# 5_SiPM.net
KiCad netlist of a schematic drawn in Altium Designer
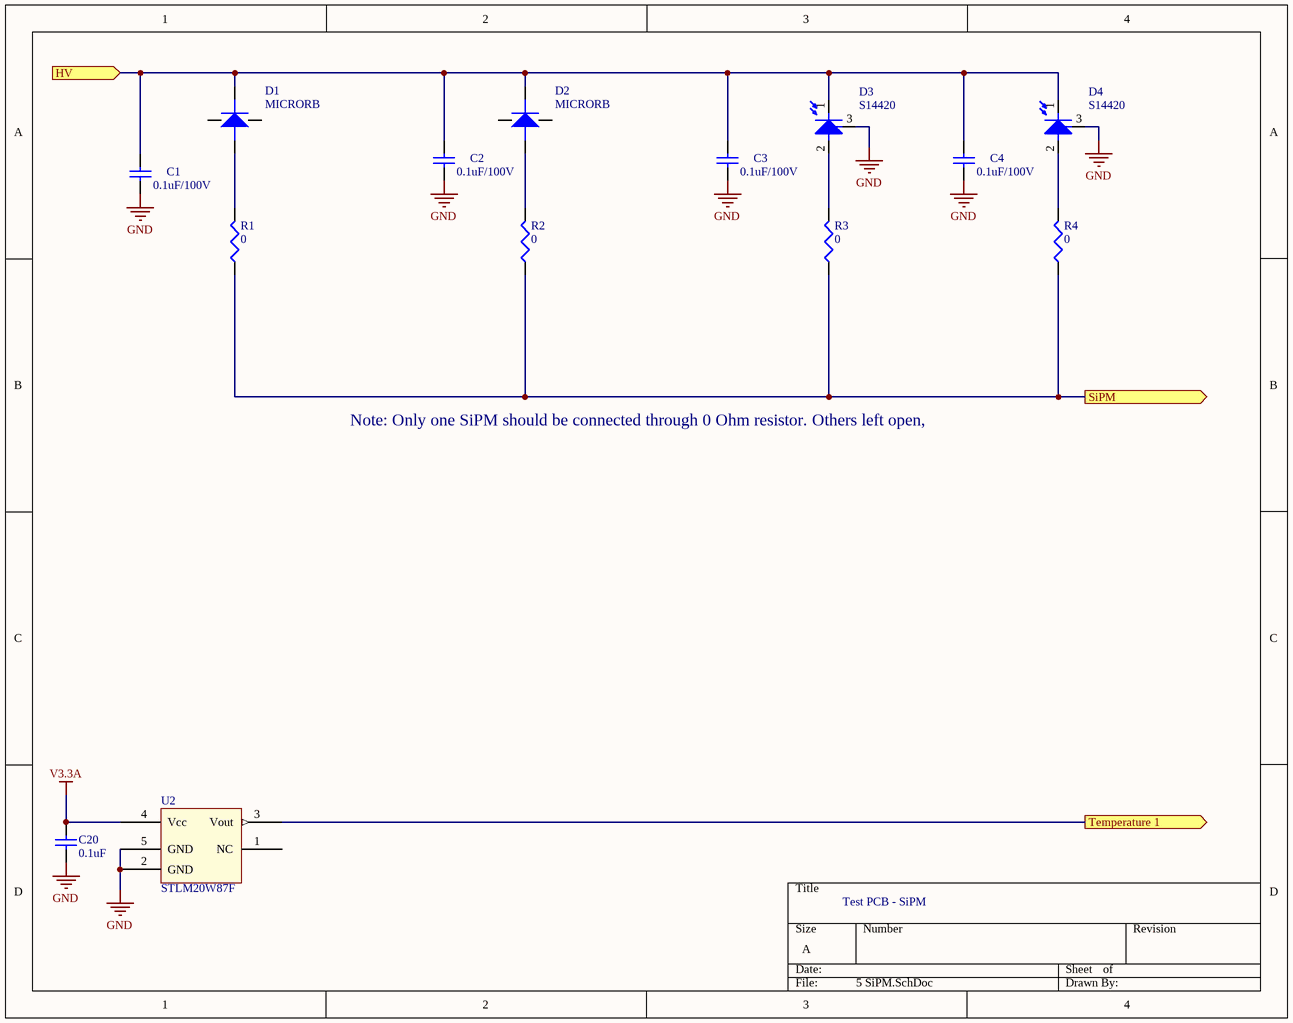
[diagram p0: 5 SiPM.SchDoc]

(export (version "E")
  (design (tool "Eeschema 10.0.6"))
  (components
    (comp (ref "C1")
      (value "0.1uF/100V")
      (footprint "C0603")
      (description "Capacitor, SM")
      (fields (field (name "PUBLISHER") "Altium Limited"))
      (libsource (lib "Graylark") (part "Cap SM"))
    )
    (comp (ref "C2")
      (value "0.1uF/100V")
      (footprint "C0603")
      (description "Capacitor, SM")
      (fields (field (name "PUBLISHER") "Altium Limited"))
      (libsource (lib "Graylark") (part "Cap SM"))
    )
    (comp (ref "C3")
      (value "0.1uF/100V")
      (footprint "C0603")
      (description "Capacitor, SM")
      (fields (field (name "PUBLISHER") "Altium Limited"))
      (libsource (lib "Graylark") (part "Cap SM"))
    )
    (comp (ref "C4")
      (value "0.1uF/100V")
      (footprint "C0603")
      (description "Capacitor, SM")
      (fields (field (name "PUBLISHER") "Altium Limited"))
      (libsource (lib "Graylark") (part "Cap SM"))
    )
    (comp (ref "C20")
      (value "0.1uF")
      (footprint "C0402")
      (description "Capacitor, SM")
      (fields (field (name "PUBLISHER") "Altium Limited"))
      (libsource (lib "Graylark") (part "Cap SM"))
    )
    (comp (ref "D1")
      (value "MICRORB")
      (footprint "MICRORB")
      (description "SiPM")
      (libsource (lib "Graylark") (part "MICRORB"))
    )
    (comp (ref "D2")
      (value "MICRORB")
      (footprint "MICRORB")
      (description "SiPM")
      (libsource (lib "Graylark") (part "MICRORB"))
    )
    (comp (ref "D3")
      (value "S14420")
      (footprint "Photodiode 3pin 200mil")
      (libsource (lib "Graylark") (part "S14420"))
    )
    (comp (ref "D4")
      (value "S14420")
      (footprint "Photodiode 3pin 200mil")
      (libsource (lib "Graylark") (part "S14420"))
    )
    (comp (ref "R1")
      (value "0")
      (footprint "R0603")
      (description "Resistor")
      (fields (field (name "PUBLISHER") "Altium Limited"))
      (libsource (lib "Graylark") (part "Res SM"))
    )
    (comp (ref "R2")
      (value "0")
      (footprint "R0603")
      (description "Resistor")
      (fields (field (name "PUBLISHER") "Altium Limited"))
      (libsource (lib "Graylark") (part "Res SM"))
    )
    (comp (ref "R3")
      (value "0")
      (footprint "R0603")
      (description "Resistor")
      (fields (field (name "PUBLISHER") "Altium Limited"))
      (libsource (lib "Graylark") (part "Res SM"))
    )
    (comp (ref "R4")
      (value "0")
      (footprint "R0603")
      (description "Resistor")
      (fields (field (name "PUBLISHER") "Altium Limited"))
      (libsource (lib "Graylark") (part "Res SM"))
    )
    (comp (ref "U2")
      (value "STLM20W87F")
      (footprint "SOT323-5")
      (libsource (lib "Graylark") (part "STML20W87F"))
    )
  )
  (nets
    (net (code "1") (name "/HV") (class "Default")
      (node (ref "C1") (pin "2") (pinfunction "2_2") (pintype "passive"))
      (node (ref "C2") (pin "2") (pinfunction "2_2") (pintype "passive"))
      (node (ref "C3") (pin "2") (pinfunction "2_2") (pintype "passive"))
      (node (ref "C4") (pin "2") (pinfunction "2_2") (pintype "passive"))
      (node (ref "D1") (pin "3") (pinfunction "Cathode_3") (pintype "passive"))
      (node (ref "D2") (pin "3") (pinfunction "Cathode_3") (pintype "passive"))
      (node (ref "D3") (pin "1") (pinfunction "K_1") (pintype "passive"))
      (node (ref "D4") (pin "1") (pinfunction "K_1") (pintype "passive"))
    )
    (net (code "2") (name "/SiPM") (class "Default")
      (node (ref "R1") (pin "1") (pinfunction "1_1") (pintype "passive"))
      (node (ref "R2") (pin "1") (pinfunction "1_1") (pintype "passive"))
      (node (ref "R3") (pin "1") (pinfunction "1_1") (pintype "passive"))
      (node (ref "R4") (pin "1") (pinfunction "1_1") (pintype "passive"))
    )
    (net (code "3") (name "/Temperature 1") (class "Default")
      (node (ref "U2") (pin "3") (pinfunction "Vout_3") (pintype "output"))
    )
    (net (code "4") (name "GND") (class "Default")
      (node (ref "C1") (pin "1") (pinfunction "1_1") (pintype "passive"))
      (node (ref "C2") (pin "1") (pinfunction "1_1") (pintype "passive"))
      (node (ref "C20") (pin "1") (pinfunction "1_1") (pintype "passive"))
      (node (ref "C3") (pin "1") (pinfunction "1_1") (pintype "passive"))
      (node (ref "C4") (pin "1") (pinfunction "1_1") (pintype "passive"))
      (node (ref "D3") (pin "3") (pinfunction "GND_3") (pintype "power_in"))
      (node (ref "D4") (pin "3") (pinfunction "GND_3") (pintype "power_in"))
      (node (ref "U2") (pin "2") (pinfunction "GND_2") (pintype "passive"))
      (node (ref "U2") (pin "5") (pinfunction "GND_5") (pintype "passive"))
    )
    (net (code "5") (name "Net-(D1-Anode)") (class "Default")
      (node (ref "D1") (pin "1") (pinfunction "Anode_1") (pintype "passive"))
      (node (ref "R1") (pin "2") (pinfunction "2_2") (pintype "passive"))
    )
    (net (code "6") (name "Net-(D2-Anode)") (class "Default")
      (node (ref "D2") (pin "1") (pinfunction "Anode_1") (pintype "passive"))
      (node (ref "R2") (pin "2") (pinfunction "2_2") (pintype "passive"))
    )
    (net (code "7") (name "Net-(D3-A)") (class "Default")
      (node (ref "D3") (pin "2") (pinfunction "A_2") (pintype "passive"))
      (node (ref "R3") (pin "2") (pinfunction "2_2") (pintype "passive"))
    )
    (net (code "8") (name "Net-(D4-A)") (class "Default")
      (node (ref "D4") (pin "2") (pinfunction "A_2") (pintype "passive"))
      (node (ref "R4") (pin "2") (pinfunction "2_2") (pintype "passive"))
    )
    (net (code "9") (name "V3.3A") (class "Default")
      (node (ref "C20") (pin "2") (pinfunction "2_2") (pintype "passive"))
      (node (ref "U2") (pin "4") (pinfunction "Vcc_4") (pintype "power_in"))
    )
    (net (code "10") (name "unconnected-(D1-Fast_output-Pad2)") (class "Default")
      (node (ref "D1") (pin "2") (pinfunction "Fast_output_2") (pintype "passive"))
    )
    (net (code "11") (name "unconnected-(D1-NC-Pad4)") (class "Default")
      (node (ref "D1") (pin "4") (pinfunction "NC_4") (pintype "passive"))
    )
    (net (code "12") (name "unconnected-(D2-Fast_output-Pad2)") (class "Default")
      (node (ref "D2") (pin "2") (pinfunction "Fast_output_2") (pintype "passive"))
    )
    (net (code "13") (name "unconnected-(D2-NC-Pad4)") (class "Default")
      (node (ref "D2") (pin "4") (pinfunction "NC_4") (pintype "passive"))
    )
    (net (code "14") (name "unconnected-(U2-NC-Pad1)") (class "Default")
      (node (ref "U2") (pin "1") (pinfunction "NC_1") (pintype "passive"))
    )
  )
)
